# EpaperTeensyBoard.net
KiCad netlist of a schematic drawn in EAGLE
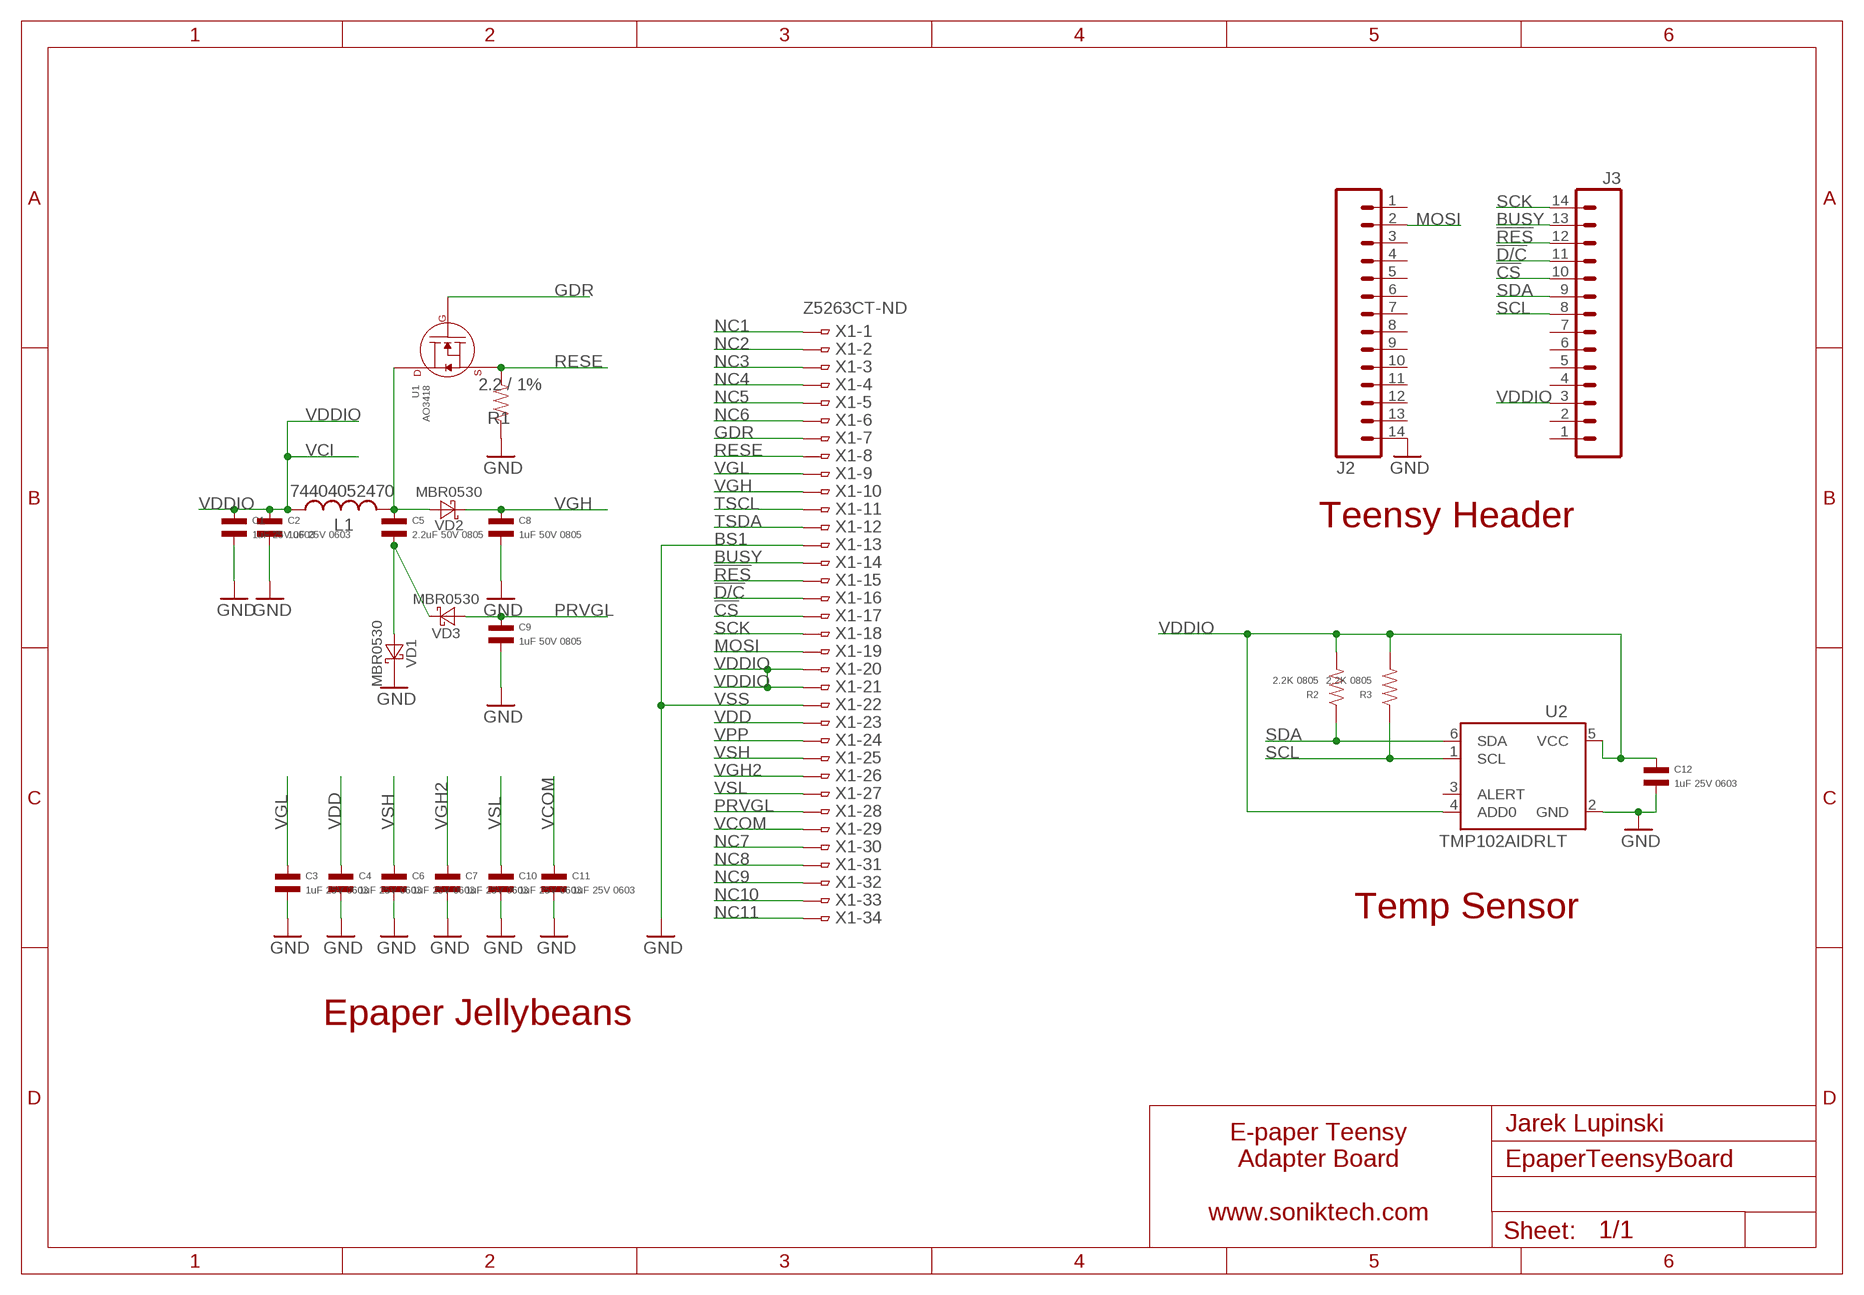
[diagram p0: schematic, sheet 1]

(export (version "E")
  (design (tool "Eeschema 10.0.6"))
  (components
    (comp (ref "C1")
      (value "1uF 25V 0603")
      (footprint "eagle-import:C0603")
      (libsource (lib "eagle-import") (part "CAPACITOR_NP_0603"))
    )
    (comp (ref "C2")
      (value "1uF 25V 0603")
      (footprint "eagle-import:C0603")
      (libsource (lib "eagle-import") (part "CAPACITOR_NP_0603"))
    )
    (comp (ref "C3")
      (value "1uF 25V 0603")
      (footprint "eagle-import:C0603")
      (libsource (lib "eagle-import") (part "CAPACITOR_NP_0603"))
    )
    (comp (ref "C4")
      (value "1uF 25V 0603")
      (footprint "eagle-import:C0603")
      (libsource (lib "eagle-import") (part "CAPACITOR_NP_0603"))
    )
    (comp (ref "C5")
      (value "2.2uF 50V 0805")
      (footprint "eagle-import:C0805")
      (libsource (lib "eagle-import") (part "CAPACITOR_NP_0805"))
    )
    (comp (ref "C6")
      (value "1uF 25V 0603")
      (footprint "eagle-import:C0603")
      (libsource (lib "eagle-import") (part "CAPACITOR_NP_0603"))
    )
    (comp (ref "C7")
      (value "1uF 25V 0603")
      (footprint "eagle-import:C0603")
      (libsource (lib "eagle-import") (part "CAPACITOR_NP_0603"))
    )
    (comp (ref "C8")
      (value "1uF 50V 0805")
      (footprint "eagle-import:C0805")
      (libsource (lib "eagle-import") (part "CAPACITOR_NP_0805"))
    )
    (comp (ref "C9")
      (value "1uF 50V 0805")
      (footprint "eagle-import:C0805")
      (libsource (lib "eagle-import") (part "CAPACITOR_NP_0805"))
    )
    (comp (ref "C10")
      (value "1uF 25V 0603")
      (footprint "eagle-import:C0603")
      (libsource (lib "eagle-import") (part "CAPACITOR_NP_0603"))
    )
    (comp (ref "C11")
      (value "1uF 25V 0603")
      (footprint "eagle-import:C0603")
      (libsource (lib "eagle-import") (part "CAPACITOR_NP_0603"))
    )
    (comp (ref "C12")
      (value "1uF 25V 0603")
      (footprint "eagle-import:C0603")
      (libsource (lib "eagle-import") (part "CAPACITOR_NP_0603"))
    )
    (comp (ref "J2")
      (value "M14")
      (footprint "eagle-import:1X14")
      (libsource (lib "eagle-import") (part "M14"))
    )
    (comp (ref "J3")
      (value "M14")
      (footprint "eagle-import:1X14")
      (libsource (lib "eagle-import") (part "M14"))
    )
    (comp (ref "L1")
      (value "74404052470")
      (footprint "eagle-import:POWER-CHOKE_WE-TPC")
      (libsource (lib "eagle-import") (part "L-USWE-TPC"))
    )
    (comp (ref "R1")
      (value "2.2 / 1%")
      (footprint "eagle-import:R0805")
      (libsource (lib "eagle-import") (part "RESISTOR_0805"))
    )
    (comp (ref "R2")
      (value "2.2K 0805")
      (footprint "eagle-import:R0805")
      (libsource (lib "eagle-import") (part "RESISTOR_0805"))
    )
    (comp (ref "R3")
      (value "2.2K 0805")
      (footprint "eagle-import:R0805")
      (libsource (lib "eagle-import") (part "RESISTOR_0805"))
    )
    (comp (ref "U1")
      (value "AO3418")
      (footprint "eagle-import:SOT-23-3")
      (fields (field (name "HOUSEPART") "NO"))
      (libsource (lib "eagle-import") (part "N-CHANNEL_FET_SOT-23-3"))
    )
    (comp (ref "U2")
      (value "TMP102AIDRLT")
      (footprint "eagle-import:SOT563")
      (libsource (lib "eagle-import") (part "TMP102"))
    )
    (comp (ref "VD1")
      (value "MBR0530")
      (footprint "eagle-import:SOD123")
      (libsource (lib "eagle-import") (part "DIODE-SCHOTTKY-SOD123"))
    )
    (comp (ref "VD2")
      (value "MBR0530")
      (footprint "eagle-import:SOD123")
      (libsource (lib "eagle-import") (part "DIODE-SCHOTTKY-SOD123"))
    )
    (comp (ref "VD3")
      (value "MBR0530")
      (footprint "eagle-import:SOD123")
      (libsource (lib "eagle-import") (part "DIODE-SCHOTTKY-SOD123"))
    )
    (comp (ref "X1")
      (value "Z5263CT-ND")
      (footprint "eagle-import:XF3M-34")
      (libsource (lib "eagle-import") (part "FH12-34S-0.5S"))
    )
  )
  (nets
    (net (code "1") (name "/BUSY") (class "Default")
      (node (ref "J3") (pin "13") (pinfunction "13_13") (pintype "passive"))
      (node (ref "X1") (pin "14") (pinfunction "1_14") (pintype "passive"))
    )
    (net (code "2") (name "/GDR") (class "Default")
      (node (ref "U1") (pin "P$1") (pinfunction "GATE_P$1") (pintype "bidirectional"))
      (node (ref "X1") (pin "7") (pinfunction "1_7") (pintype "passive"))
    )
    (net (code "3") (name "/MOSI") (class "Default")
      (node (ref "J2") (pin "2") (pinfunction "2_2") (pintype "passive"))
      (node (ref "X1") (pin "19") (pinfunction "1_19") (pintype "passive"))
    )
    (net (code "4") (name "/NC1") (class "Default")
      (node (ref "X1") (pin "1") (pinfunction "1_1") (pintype "passive"))
    )
    (net (code "5") (name "/NC2") (class "Default")
      (node (ref "X1") (pin "2") (pinfunction "1_2") (pintype "passive"))
    )
    (net (code "6") (name "/NC3") (class "Default")
      (node (ref "X1") (pin "3") (pinfunction "1_3") (pintype "passive"))
    )
    (net (code "7") (name "/NC4") (class "Default")
      (node (ref "X1") (pin "4") (pinfunction "1_4") (pintype "passive"))
    )
    (net (code "8") (name "/NC5") (class "Default")
      (node (ref "X1") (pin "5") (pinfunction "1_5") (pintype "passive"))
    )
    (net (code "9") (name "/NC6") (class "Default")
      (node (ref "X1") (pin "6") (pinfunction "1_6") (pintype "passive"))
    )
    (net (code "10") (name "/NC7") (class "Default")
      (node (ref "X1") (pin "30") (pinfunction "1_30") (pintype "passive"))
    )
    (net (code "11") (name "/NC8") (class "Default")
      (node (ref "X1") (pin "31") (pinfunction "1_31") (pintype "passive"))
    )
    (net (code "12") (name "/NC9") (class "Default")
      (node (ref "X1") (pin "32") (pinfunction "1_32") (pintype "passive"))
    )
    (net (code "13") (name "/NC10") (class "Default")
      (node (ref "X1") (pin "33") (pinfunction "1_33") (pintype "passive"))
    )
    (net (code "14") (name "/NC11") (class "Default")
      (node (ref "X1") (pin "34") (pinfunction "1_34") (pintype "passive"))
    )
    (net (code "15") (name "/PRVGL") (class "Default")
      (node (ref "C9") (pin "P$1") (pinfunction "P$1_P$1") (pintype "passive"))
      (node (ref "VD3") (pin "A") (pinfunction "A_A") (pintype "passive"))
      (node (ref "X1") (pin "28") (pinfunction "1_28") (pintype "passive"))
    )
    (net (code "16") (name "/RESE") (class "Default")
      (node (ref "R1") (pin "P$2") (pinfunction "P$2_P$2") (pintype "passive"))
      (node (ref "U1") (pin "P$2") (pinfunction "SOURCE_P$2") (pintype "bidirectional"))
      (node (ref "X1") (pin "8") (pinfunction "1_8") (pintype "passive"))
    )
    (net (code "17") (name "/SCK") (class "Default")
      (node (ref "J3") (pin "14") (pinfunction "14_14") (pintype "passive"))
      (node (ref "X1") (pin "18") (pinfunction "1_18") (pintype "passive"))
    )
    (net (code "18") (name "/SCL") (class "Default")
      (node (ref "J3") (pin "8") (pinfunction "8_8") (pintype "passive"))
      (node (ref "R3") (pin "P$1") (pinfunction "P$1_P$1") (pintype "passive"))
      (node (ref "U2") (pin "1") (pinfunction "SCL_1") (pintype "bidirectional"))
    )
    (net (code "19") (name "/SDA") (class "Default")
      (node (ref "J3") (pin "9") (pinfunction "9_9") (pintype "passive"))
      (node (ref "R2") (pin "P$1") (pinfunction "P$1_P$1") (pintype "passive"))
      (node (ref "U2") (pin "6") (pinfunction "SDA_6") (pintype "bidirectional"))
    )
    (net (code "20") (name "/TSCL") (class "Default")
      (node (ref "X1") (pin "11") (pinfunction "1_11") (pintype "passive"))
    )
    (net (code "21") (name "/TSDA") (class "Default")
      (node (ref "X1") (pin "12") (pinfunction "1_12") (pintype "passive"))
    )
    (net (code "22") (name "/VCOM") (class "Default")
      (node (ref "C11") (pin "P$1") (pinfunction "P$1_P$1") (pintype "passive"))
      (node (ref "X1") (pin "29") (pinfunction "1_29") (pintype "passive"))
    )
    (net (code "23") (name "/VDD") (class "Default")
      (node (ref "C4") (pin "P$1") (pinfunction "P$1_P$1") (pintype "passive"))
      (node (ref "X1") (pin "23") (pinfunction "1_23") (pintype "passive"))
    )
    (net (code "24") (name "/VDDIO") (class "Default")
      (node (ref "C1") (pin "P$1") (pinfunction "P$1_P$1") (pintype "passive"))
      (node (ref "C12") (pin "P$1") (pinfunction "P$1_P$1") (pintype "passive"))
      (node (ref "C2") (pin "P$1") (pinfunction "P$1_P$1") (pintype "passive"))
      (node (ref "J3") (pin "3") (pinfunction "3_3") (pintype "passive"))
      (node (ref "L1") (pin "1") (pinfunction "1_1") (pintype "passive"))
      (node (ref "R2") (pin "P$2") (pinfunction "P$2_P$2") (pintype "passive"))
      (node (ref "R3") (pin "P$2") (pinfunction "P$2_P$2") (pintype "passive"))
      (node (ref "U2") (pin "4") (pinfunction "ADD0_4") (pintype "bidirectional"))
      (node (ref "U2") (pin "5") (pinfunction "VCC_5") (pintype "bidirectional"))
      (node (ref "X1") (pin "20") (pinfunction "1_20") (pintype "passive"))
      (node (ref "X1") (pin "21") (pinfunction "1_21") (pintype "passive"))
    )
    (net (code "25") (name "/VGH") (class "Default")
      (node (ref "C8") (pin "P$1") (pinfunction "P$1_P$1") (pintype "passive"))
      (node (ref "VD2") (pin "C") (pinfunction "C_C") (pintype "passive"))
      (node (ref "X1") (pin "10") (pinfunction "1_10") (pintype "passive"))
    )
    (net (code "26") (name "/VGH2") (class "Default")
      (node (ref "C7") (pin "P$1") (pinfunction "P$1_P$1") (pintype "passive"))
      (node (ref "X1") (pin "26") (pinfunction "1_26") (pintype "passive"))
    )
    (net (code "27") (name "/VGL") (class "Default")
      (node (ref "C3") (pin "P$1") (pinfunction "P$1_P$1") (pintype "passive"))
      (node (ref "X1") (pin "9") (pinfunction "1_9") (pintype "passive"))
    )
    (net (code "28") (name "/VPP") (class "Default")
      (node (ref "X1") (pin "24") (pinfunction "1_24") (pintype "passive"))
    )
    (net (code "29") (name "/VSH") (class "Default")
      (node (ref "C6") (pin "P$1") (pinfunction "P$1_P$1") (pintype "passive"))
      (node (ref "X1") (pin "25") (pinfunction "1_25") (pintype "passive"))
    )
    (net (code "30") (name "/VSL") (class "Default")
      (node (ref "C10") (pin "P$1") (pinfunction "P$1_P$1") (pintype "passive"))
      (node (ref "X1") (pin "27") (pinfunction "1_27") (pintype "passive"))
    )
    (net (code "31") (name "/~{CS}") (class "Default")
      (node (ref "J3") (pin "10") (pinfunction "10_10") (pintype "passive"))
      (node (ref "X1") (pin "17") (pinfunction "1_17") (pintype "passive"))
    )
    (net (code "32") (name "/~{D{slash}C}") (class "Default")
      (node (ref "J3") (pin "11") (pinfunction "11_11") (pintype "passive"))
      (node (ref "X1") (pin "16") (pinfunction "1_16") (pintype "passive"))
    )
    (net (code "33") (name "/~{RES}") (class "Default")
      (node (ref "J3") (pin "12") (pinfunction "12_12") (pintype "passive"))
      (node (ref "X1") (pin "15") (pinfunction "1_15") (pintype "passive"))
    )
    (net (code "34") (name "GND") (class "Default")
      (node (ref "C1") (pin "P$2") (pinfunction "P$2_P$2") (pintype "passive"))
      (node (ref "C10") (pin "P$2") (pinfunction "P$2_P$2") (pintype "passive"))
      (node (ref "C11") (pin "P$2") (pinfunction "P$2_P$2") (pintype "passive"))
      (node (ref "C12") (pin "P$2") (pinfunction "P$2_P$2") (pintype "passive"))
      (node (ref "C2") (pin "P$2") (pinfunction "P$2_P$2") (pintype "passive"))
      (node (ref "C3") (pin "P$2") (pinfunction "P$2_P$2") (pintype "passive"))
      (node (ref "C4") (pin "P$2") (pinfunction "P$2_P$2") (pintype "passive"))
      (node (ref "C6") (pin "P$2") (pinfunction "P$2_P$2") (pintype "passive"))
      (node (ref "C7") (pin "P$2") (pinfunction "P$2_P$2") (pintype "passive"))
      (node (ref "C8") (pin "P$2") (pinfunction "P$2_P$2") (pintype "passive"))
      (node (ref "C9") (pin "P$2") (pinfunction "P$2_P$2") (pintype "passive"))
      (node (ref "J2") (pin "14") (pinfunction "14_14") (pintype "passive"))
      (node (ref "R1") (pin "P$1") (pinfunction "P$1_P$1") (pintype "passive"))
      (node (ref "U2") (pin "2") (pinfunction "GND_2") (pintype "bidirectional"))
      (node (ref "VD1") (pin "C") (pinfunction "C_C") (pintype "passive"))
      (node (ref "X1") (pin "13") (pinfunction "1_13") (pintype "passive"))
      (node (ref "X1") (pin "22") (pinfunction "1_22") (pintype "passive"))
    )
    (net (code "35") (name "Net-(C5-PadP$2)") (class "Default")
      (node (ref "C5") (pin "P$2") (pinfunction "P$2_P$2") (pintype "passive"))
      (node (ref "VD1") (pin "A") (pinfunction "A_A") (pintype "passive"))
      (node (ref "VD3") (pin "C") (pinfunction "C_C") (pintype "passive"))
    )
    (net (code "36") (name "Net-(U1-DRAIN)") (class "Default")
      (node (ref "C5") (pin "P$1") (pinfunction "P$1_P$1") (pintype "passive"))
      (node (ref "L1") (pin "2") (pinfunction "2_2") (pintype "passive"))
      (node (ref "U1") (pin "P$3") (pinfunction "DRAIN_P$3") (pintype "bidirectional"))
      (node (ref "VD2") (pin "A") (pinfunction "A_A") (pintype "passive"))
    )
    (net (code "37") (name "unconnected-(J2-Pad1)") (class "Default")
      (node (ref "J2") (pin "1") (pinfunction "1_1") (pintype "passive"))
    )
    (net (code "38") (name "unconnected-(J2-Pad3)") (class "Default")
      (node (ref "J2") (pin "3") (pinfunction "3_3") (pintype "passive"))
    )
    (net (code "39") (name "unconnected-(J2-Pad4)") (class "Default")
      (node (ref "J2") (pin "4") (pinfunction "4_4") (pintype "passive"))
    )
    (net (code "40") (name "unconnected-(J2-Pad5)") (class "Default")
      (node (ref "J2") (pin "5") (pinfunction "5_5") (pintype "passive"))
    )
    (net (code "41") (name "unconnected-(J2-Pad6)") (class "Default")
      (node (ref "J2") (pin "6") (pinfunction "6_6") (pintype "passive"))
    )
    (net (code "42") (name "unconnected-(J2-Pad7)") (class "Default")
      (node (ref "J2") (pin "7") (pinfunction "7_7") (pintype "passive"))
    )
    (net (code "43") (name "unconnected-(J2-Pad8)") (class "Default")
      (node (ref "J2") (pin "8") (pinfunction "8_8") (pintype "passive"))
    )
    (net (code "44") (name "unconnected-(J2-Pad9)") (class "Default")
      (node (ref "J2") (pin "9") (pinfunction "9_9") (pintype "passive"))
    )
    (net (code "45") (name "unconnected-(J2-Pad10)") (class "Default")
      (node (ref "J2") (pin "10") (pinfunction "10_10") (pintype "passive"))
    )
    (net (code "46") (name "unconnected-(J2-Pad11)") (class "Default")
      (node (ref "J2") (pin "11") (pinfunction "11_11") (pintype "passive"))
    )
    (net (code "47") (name "unconnected-(J2-Pad12)") (class "Default")
      (node (ref "J2") (pin "12") (pinfunction "12_12") (pintype "passive"))
    )
    (net (code "48") (name "unconnected-(J2-Pad13)") (class "Default")
      (node (ref "J2") (pin "13") (pinfunction "13_13") (pintype "passive"))
    )
    (net (code "49") (name "unconnected-(J3-Pad1)") (class "Default")
      (node (ref "J3") (pin "1") (pinfunction "1_1") (pintype "passive"))
    )
    (net (code "50") (name "unconnected-(J3-Pad2)") (class "Default")
      (node (ref "J3") (pin "2") (pinfunction "2_2") (pintype "passive"))
    )
    (net (code "51") (name "unconnected-(J3-Pad4)") (class "Default")
      (node (ref "J3") (pin "4") (pinfunction "4_4") (pintype "passive"))
    )
    (net (code "52") (name "unconnected-(J3-Pad5)") (class "Default")
      (node (ref "J3") (pin "5") (pinfunction "5_5") (pintype "passive"))
    )
    (net (code "53") (name "unconnected-(J3-Pad6)") (class "Default")
      (node (ref "J3") (pin "6") (pinfunction "6_6") (pintype "passive"))
    )
    (net (code "54") (name "unconnected-(J3-Pad7)") (class "Default")
      (node (ref "J3") (pin "7") (pinfunction "7_7") (pintype "passive"))
    )
    (net (code "55") (name "unconnected-(U2-ALERT-Pad3)") (class "Default")
      (node (ref "U2") (pin "3") (pinfunction "ALERT_3") (pintype "bidirectional"))
    )
  )
)
